# Qunyin_mmWave_mainIOs.net
KiCad netlist of a schematic drawn in Altium Designer
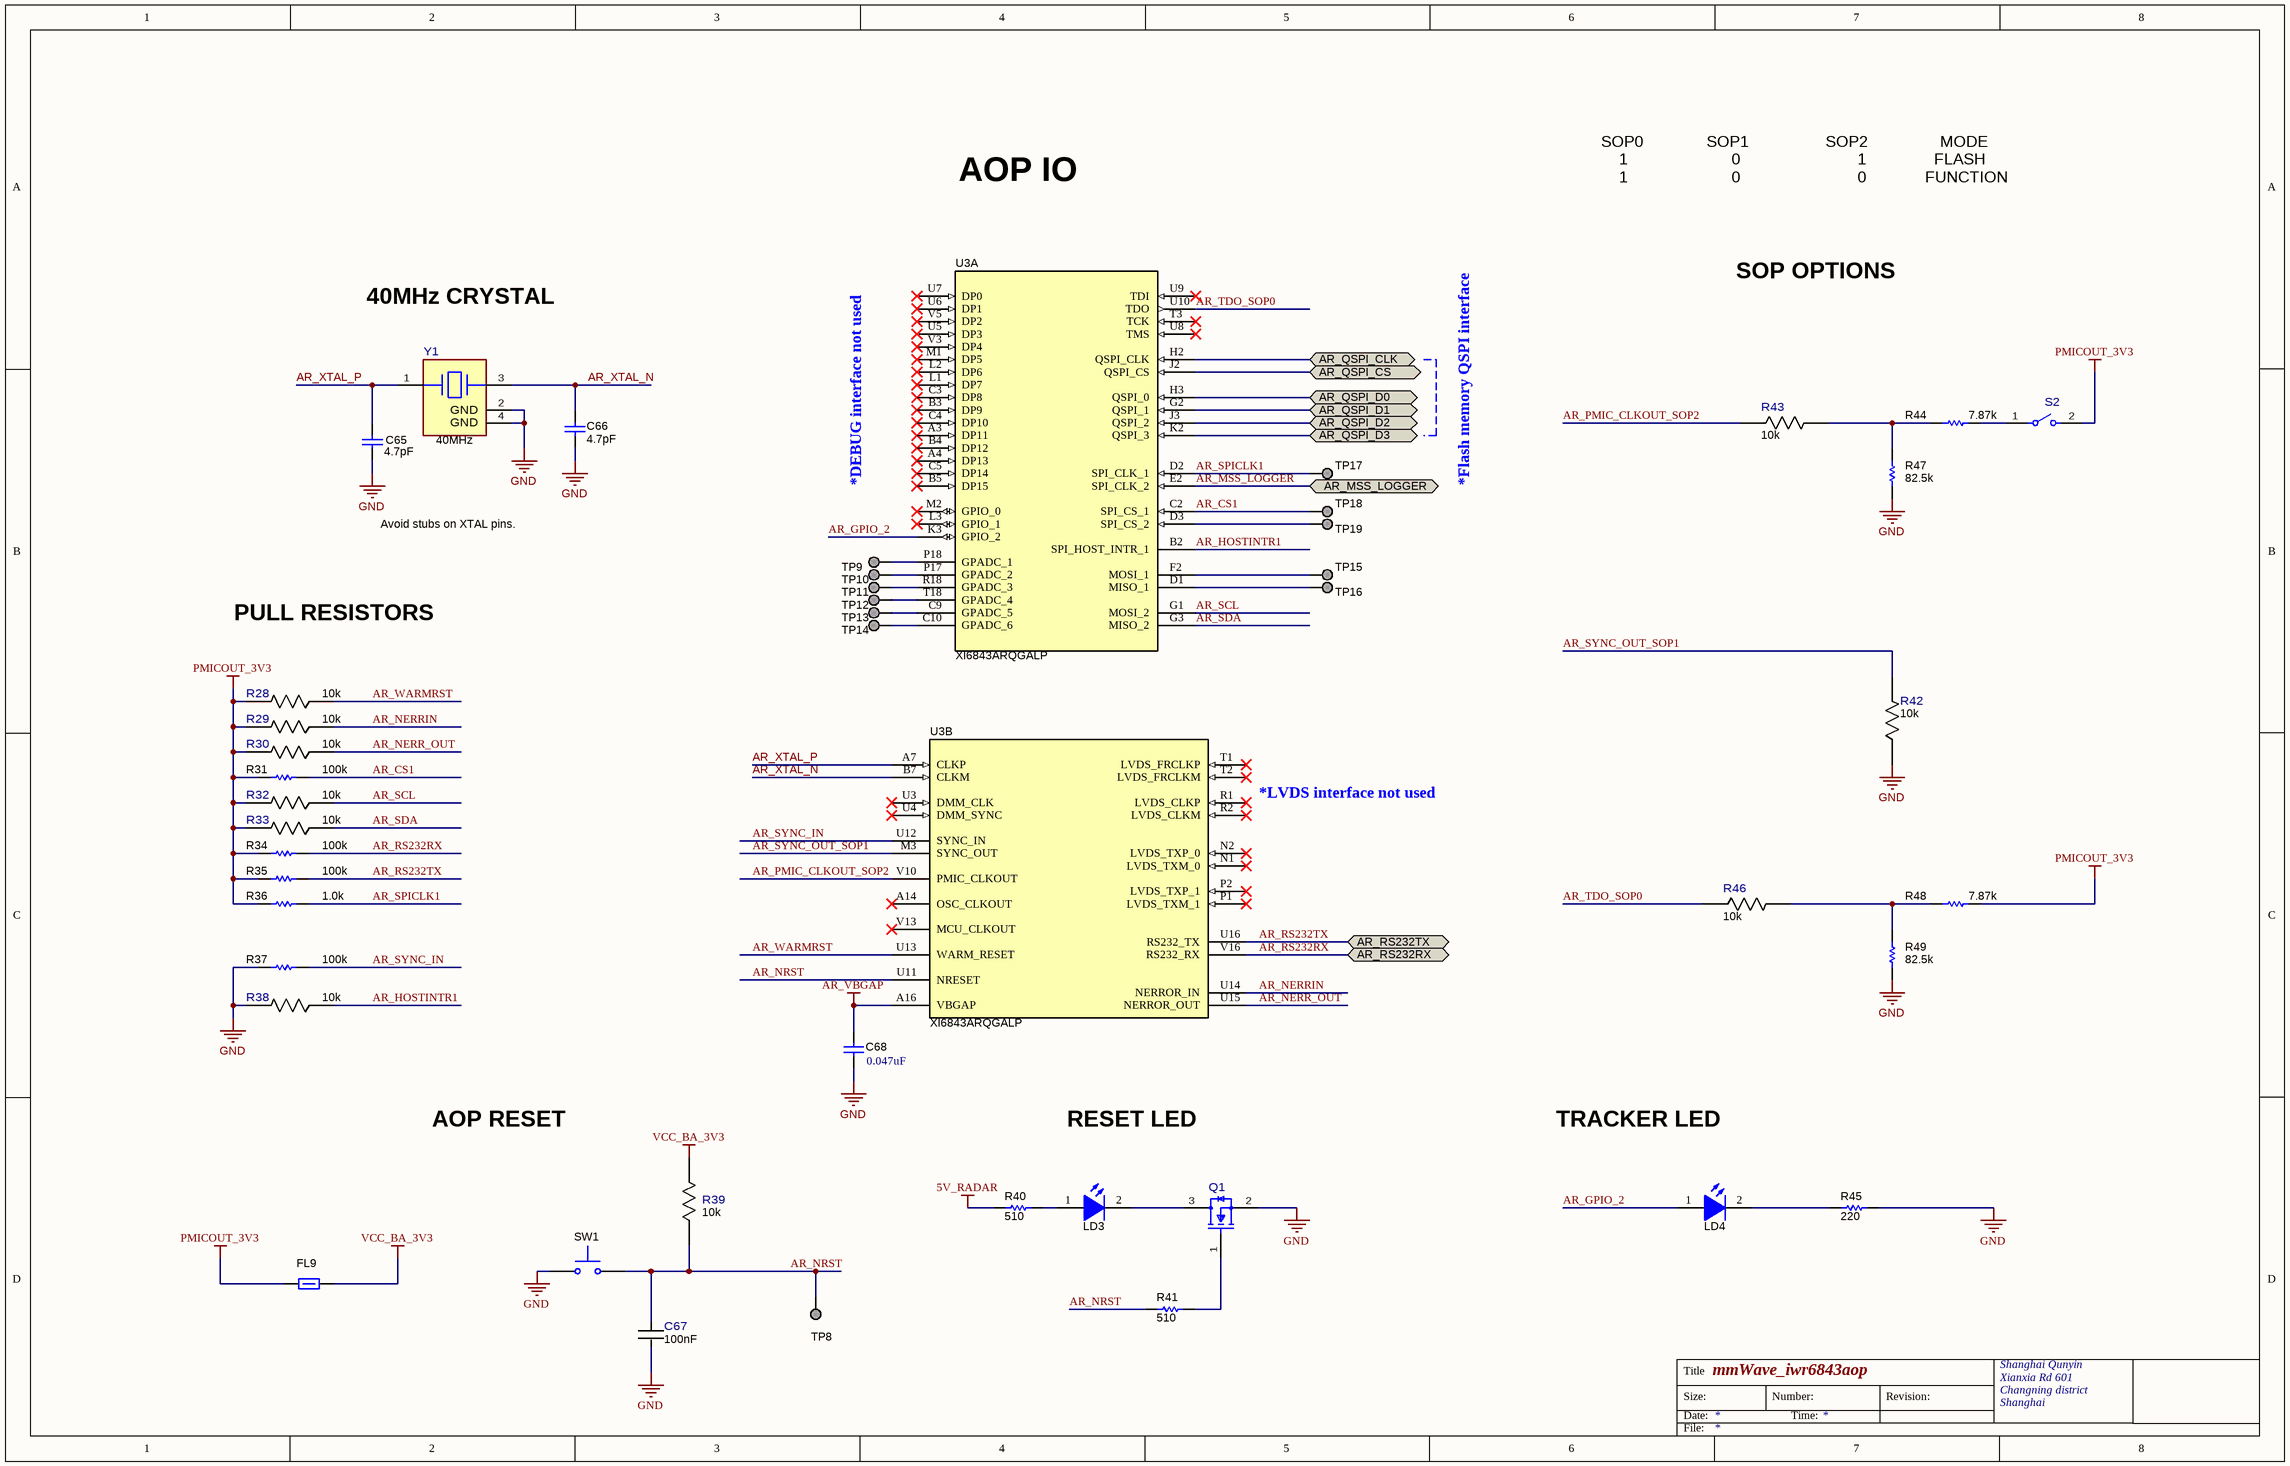
[diagram p0: Qunyin_mmWave_mainIOs.SchDoc]

(export (version "E")
  (design (tool "Eeschema 10.0.6"))
  (components
    (comp (ref "C65")
      (value "4.7pF")
      (footprint "0201_033L")
      (description "CAP, CERM, 4.7 pF, 50 V,+/- 3%, C0G/NP0, 0201")
      (fields (field (name "MANUFACTURER") "MuRata") (field (name "PARTNUMBER") "GRM0335C1H4R7BA01D"))
      (libsource (lib "Altium Vault - TI") (part "Capacitor"))
    )
    (comp (ref "C66")
      (value "4.7pF")
      (footprint "0201_033L")
      (description "CAP, CERM, 4.7 pF, 50 V,+/- 3%, C0G/NP0, 0201")
      (fields (field (name "MANUFACTURER") "MuRata") (field (name "PARTNUMBER") "GRM0335C1H4R7BA01D"))
      (libsource (lib "Altium Vault - TI") (part "Capacitor"))
    )
    (comp (ref "C67")
      (value "GRM033R6YA104KE14D")
      (footprint "FP-GRM033R6YA104KE14D_0201 (0603 Metric)-IPC_C")
      (description "Cap Ceramic 0.1uF 35V X5R 10% Pad SMD 0201 85C T/R")
      (fields (field (name "CAP_F") "100nF") (field (name "MANUFACTURER") "Murata Electronics North America"))
      (libsource (lib "Altium Vault - TI") (part "SYM-B32642B0223J"))
    )
    (comp (ref "C68")
      (value "GRM033R61C473KE84D")
      (footprint "0201_033L")
      (description "CAP, CERM, 0.047 uF, 16 V, +/- 10%, X5R, 0201")
      (fields
        (field (name "MANUFACTURER") "MuRata")
        (field (name "VALUEDISPLAYED") "0.047uF")
        (field (name "PUBLISHER") "Texas Instruments")
      )
      (libsource (lib "Altium Vault - TI") (part "Capacitor"))
    )
    (comp (ref "FL9")
      (value "BLM15PD300SZ1D")
      (footprint "0402L")
      (description "Inductor, Ferrite Bead, Ferrite, 2.2 A, 0.035 ohm, AEC-Q200 Grade 1, SMD")
      (fields (field (name "MANUFACTURER") "MuRata") (field (name "PUBLISHER") "Texas Instruments"))
      (libsource (lib "Altium Vault - TI") (part "Ferrite_Bead"))
    )
    (comp (ref "LD3")
      (value "APHHS1005CGCK")
      (footprint "APHHS1005_Green")
      (description "LED, Green, SMD")
      (fields (field (name "MANUFACTURER") "Kingbright"))
      (libsource (lib "Altium Vault - TI") (part "LED"))
    )
    (comp (ref "LD4")
      (value "APHHS1005CGCK")
      (footprint "APHHS1005_Green")
      (description "LED, Green, SMD")
      (fields (field (name "MANUFACTURER") "Kingbright"))
      (libsource (lib "Altium Vault - TI") (part "LED"))
    )
    (comp (ref "Q1")
      (value "BSS123-7-F")
      (footprint "FP-BSS123-7-F_SOT23-IPC_C")
      (description "MOSFET N-CH 100V 170MA SOT23-3")
      (fields (field (name "MANUFACTURER") "Diodes Incorporated"))
      (libsource (lib "Altium Vault - TI") (part "SYM-BSS123-7-F"))
    )
    (comp (ref "R28")
      (value "RR0306P-103-D")
      (footprint "FP-RR0306P-103-D_0201-IPC_C")
      (description "10 kOhms ±0.5% 0.05W, 1/20W Chip Resistor 0201 (0603 Metric)  Thin Film")
      (fields (field (name "MANUFACTURER") "Susumu") (field (name "RES_OHM") "10k"))
      (libsource (lib "Altium Vault - TI") (part "SYM-PMR18EZPJ000"))
    )
    (comp (ref "R29")
      (value "RR0306P-103-D")
      (footprint "FP-RR0306P-103-D_0201-IPC_C")
      (description "10 kOhms ±0.5% 0.05W, 1/20W Chip Resistor 0201 (0603 Metric)  Thin Film")
      (fields (field (name "MANUFACTURER") "Susumu") (field (name "RES_OHM") "10k"))
      (libsource (lib "Altium Vault - TI") (part "SYM-PMR18EZPJ000"))
    )
    (comp (ref "R30")
      (value "RR0306P-103-D")
      (footprint "FP-RR0306P-103-D_0201-IPC_C")
      (description "10 kOhms ±0.5% 0.05W, 1/20W Chip Resistor 0201 (0603 Metric)  Thin Film")
      (fields (field (name "MANUFACTURER") "Susumu") (field (name "RES_OHM") "10k"))
      (libsource (lib "Altium Vault - TI") (part "SYM-PMR18EZPJ000"))
    )
    (comp (ref "R31")
      (value "100k")
      (footprint "0201L")
      (description "RES, 100 k, 1%, 0.05 W, 0201")
      (fields (field (name "MANUFACTURER") "Vishay-Dale") (field (name "PARTNUMBER") "CRCW0201100KFKED"))
      (libsource (lib "Altium Vault - TI") (part "Resistor"))
    )
    (comp (ref "R32")
      (value "RR0306P-103-D")
      (footprint "FP-RR0306P-103-D_0201-IPC_C")
      (description "10 kOhms ±0.5% 0.05W, 1/20W Chip Resistor 0201 (0603 Metric)  Thin Film")
      (fields (field (name "MANUFACTURER") "Susumu") (field (name "RES_OHM") "10k"))
      (libsource (lib "Altium Vault - TI") (part "SYM-PMR18EZPJ000"))
    )
    (comp (ref "R33")
      (value "RR0306P-103-D")
      (footprint "FP-RR0306P-103-D_0201-IPC_C")
      (description "10 kOhms ±0.5% 0.05W, 1/20W Chip Resistor 0201 (0603 Metric)  Thin Film")
      (fields (field (name "MANUFACTURER") "Susumu") (field (name "RES_OHM") "10k"))
      (libsource (lib "Altium Vault - TI") (part "SYM-PMR18EZPJ000"))
    )
    (comp (ref "R34")
      (value "100k")
      (footprint "0201L")
      (description "RES, 100 k, 1%, 0.05 W, 0201")
      (fields (field (name "MANUFACTURER") "Vishay-Dale") (field (name "PARTNUMBER") "CRCW0201100KFKED"))
      (libsource (lib "Altium Vault - TI") (part "Resistor"))
    )
    (comp (ref "R35")
      (value "100k")
      (footprint "0201L")
      (description "RES, 100 k, 1%, 0.05 W, 0201")
      (fields (field (name "MANUFACTURER") "Vishay-Dale") (field (name "PARTNUMBER") "CRCW0201100KFKED"))
      (libsource (lib "Altium Vault - TI") (part "Resistor"))
    )
    (comp (ref "R36")
      (value "1.0k")
      (footprint "0201L")
      (description "RES, 1.0 k, 5%, 0.05 W, 0201")
      (fields
        (field (name "MANUFACTURER") "Yageo America")
        (field (name "PARTNUMBER") "RC0201JR-071KL")
        (field (name "PUBLISHER") "Texas Instruments")
      )
      (libsource (lib "Altium Vault - TI") (part "Resistor"))
    )
    (comp (ref "R37")
      (value "100k")
      (footprint "0201L")
      (description "RES, 100 k, 1%, 0.05 W, 0201")
      (fields (field (name "MANUFACTURER") "Vishay-Dale") (field (name "PARTNUMBER") "CRCW0201100KFKED"))
      (libsource (lib "Altium Vault - TI") (part "Resistor"))
    )
    (comp (ref "R38")
      (value "RR0306P-103-D")
      (footprint "FP-RR0306P-103-D_0201-IPC_C")
      (description "10 kOhms ±0.5% 0.05W, 1/20W Chip Resistor 0201 (0603 Metric)  Thin Film")
      (fields (field (name "MANUFACTURER") "Susumu") (field (name "RES_OHM") "10k"))
      (libsource (lib "Altium Vault - TI") (part "SYM-PMR18EZPJ000"))
    )
    (comp (ref "R39")
      (value "RR0306P-103-D")
      (footprint "FP-RR0306P-103-D_0201-IPC_C")
      (description "10 kOhms ±0.5% 0.05W, 1/20W Chip Resistor 0201 (0603 Metric)  Thin Film")
      (fields (field (name "MANUFACTURER") "Susumu") (field (name "RES_OHM") "10k"))
      (libsource (lib "Altium Vault - TI") (part "SYM-PMR18EZPJ000"))
    )
    (comp (ref "R40")
      (value "510")
      (footprint "0201L")
      (description "RES, 510, 5%, 0.05 W, 0201")
      (fields
        (field (name "MANUFACTURER") "Yageo America")
        (field (name "PARTNUMBER") "RC0201JR-07510RL")
        (field (name "PUBLISHER") "Texas Instruments")
      )
      (libsource (lib "Altium Vault - TI") (part "Resistor"))
    )
    (comp (ref "R41")
      (value "510")
      (footprint "0201L")
      (description "RES, 510, 5%, 0.05 W, 0201")
      (fields
        (field (name "MANUFACTURER") "Yageo America")
        (field (name "PARTNUMBER") "RC0201JR-07510RL")
        (field (name "PUBLISHER") "Texas Instruments")
      )
      (libsource (lib "Altium Vault - TI") (part "Resistor"))
    )
    (comp (ref "R42")
      (value "RR0306P-103-D")
      (footprint "FP-RR0306P-103-D_0201-IPC_C")
      (description "10 kOhms ±0.5% 0.05W, 1/20W Chip Resistor 0201 (0603 Metric)  Thin Film")
      (fields (field (name "MANUFACTURER") "Susumu") (field (name "RES_OHM") "10k"))
      (libsource (lib "Altium Vault - TI") (part "SYM-PMR18EZPJ000"))
    )
    (comp (ref "R43")
      (value "RR0306P-103-D")
      (footprint "FP-RR0306P-103-D_0201-IPC_C")
      (description "10 kOhms ±0.5% 0.05W, 1/20W Chip Resistor 0201 (0603 Metric)  Thin Film")
      (fields (field (name "MANUFACTURER") "Susumu") (field (name "RES_OHM") "10k"))
      (libsource (lib "Altium Vault - TI") (part "SYM-PMR18EZPJ000"))
    )
    (comp (ref "R44")
      (value "7.87k")
      (footprint "0201L")
      (description "RES, 7.87 k, 1%, 0.05 W, 0201")
      (fields
        (field (name "MANUFACTURER") "Yageo America")
        (field (name "PARTNUMBER") "RC0201FR-077K87L")
        (field (name "PUBLISHER") "Texas Instruments")
      )
      (libsource (lib "Altium Vault - TI") (part "Resistor"))
    )
    (comp (ref "R45")
      (value "220")
      (footprint "0201L")
      (description "RES, 220, 5%, 0.05 W, 0201")
      (fields
        (field (name "MANUFACTURER") "Yageo America")
        (field (name "PARTNUMBER") "RC0201JR-07220RL")
        (field (name "PUBLISHER") "Texas Instruments")
      )
      (libsource (lib "Altium Vault - TI") (part "Resistor"))
    )
    (comp (ref "R46")
      (value "RR0306P-103-D")
      (footprint "FP-RR0306P-103-D_0201-IPC_C")
      (description "10 kOhms ±0.5% 0.05W, 1/20W Chip Resistor 0201 (0603 Metric)  Thin Film")
      (fields (field (name "MANUFACTURER") "Susumu") (field (name "RES_OHM") "10k"))
      (libsource (lib "Altium Vault - TI") (part "SYM-PMR18EZPJ000"))
    )
    (comp (ref "R47")
      (value "82.5k")
      (footprint "0201L")
      (description "RES, 82.5 k, 1%, 0.05 W, 0201")
      (fields
        (field (name "MANUFACTURER") "Yageo America")
        (field (name "PARTNUMBER") "RC0201FR-0782K5L")
        (field (name "PUBLISHER") "Texas Instruments")
      )
      (libsource (lib "Altium Vault - TI") (part "Resistor"))
    )
    (comp (ref "R48")
      (value "7.87k")
      (footprint "0201L")
      (description "RES, 7.87 k, 1%, 0.05 W, 0201")
      (fields
        (field (name "MANUFACTURER") "Yageo America")
        (field (name "PARTNUMBER") "RC0201FR-077K87L")
        (field (name "PUBLISHER") "Texas Instruments")
      )
      (libsource (lib "Altium Vault - TI") (part "Resistor"))
    )
    (comp (ref "R49")
      (value "82.5k")
      (footprint "0201L")
      (description "RES, 82.5 k, 1%, 0.05 W, 0201")
      (fields
        (field (name "MANUFACTURER") "Yageo America")
        (field (name "PARTNUMBER") "RC0201FR-0782K5L")
        (field (name "PUBLISHER") "Texas Instruments")
      )
      (libsource (lib "Altium Vault - TI") (part "Resistor"))
    )
    (comp (ref "S2")
      (value "CHS-01TA")
      (footprint "FP-CHS-01TA_SMT_SW_5MM4_2MM5-MFG")
      (description "SWITCH SLIDE DIP SPST 100MA 6V")
      (fields (field (name "MANUFACTURER") "Nidec Copal Electronics"))
      (libsource (lib "Altium Vault - TI") (part "SYM-PTS635SK25SM"))
    )
    (comp (ref "SW1")
      (value "B3U-1000P")
      (footprint "SW_B3U-1000P")
      (description "SWITCH TACTILE SPST-NO 0.05A 12V")
      (fields
        (field (name "MANUFACTURER") "Omron Electronic Components")
        (field (name "PUBLISHER") "Texas Instruments")
      )
      (libsource (lib "Altium Vault - TI") (part "Switch_PushButton"))
    )
    (comp (ref "TP8")
      (value "TESTPOINT")
      (footprint "TP_25MIL-SMT")
      (description "TEST POINT.  No entry in BOM.")
      (libsource (lib "Altium Vault - TI") (part "TESTPOINT"))
    )
    (comp (ref "TP9")
      (value "TESTPOINT")
      (footprint "TP_25MIL-SMT")
      (description "TEST POINT.  No entry in BOM.")
      (libsource (lib "Altium Vault - TI") (part "TESTPOINT"))
    )
    (comp (ref "TP10")
      (value "TESTPOINT")
      (footprint "TP_25MIL-SMT")
      (description "TEST POINT.  No entry in BOM.")
      (libsource (lib "Altium Vault - TI") (part "TESTPOINT"))
    )
    (comp (ref "TP11")
      (value "TESTPOINT")
      (footprint "TP_25MIL-SMT")
      (description "TEST POINT.  No entry in BOM.")
      (libsource (lib "Altium Vault - TI") (part "TESTPOINT"))
    )
    (comp (ref "TP12")
      (value "TESTPOINT")
      (footprint "TP_25MIL-SMT")
      (description "TEST POINT.  No entry in BOM.")
      (libsource (lib "Altium Vault - TI") (part "TESTPOINT"))
    )
    (comp (ref "TP13")
      (value "TESTPOINT")
      (footprint "TP_25MIL-SMT")
      (description "TEST POINT.  No entry in BOM.")
      (libsource (lib "Altium Vault - TI") (part "TESTPOINT"))
    )
    (comp (ref "TP14")
      (value "TESTPOINT")
      (footprint "TP_25MIL-SMT")
      (description "TEST POINT.  No entry in BOM.")
      (libsource (lib "Altium Vault - TI") (part "TESTPOINT"))
    )
    (comp (ref "TP15")
      (value "TESTPOINT")
      (footprint "TP_25MIL-SMT")
      (description "TEST POINT.  No entry in BOM.")
      (libsource (lib "Altium Vault - TI") (part "TESTPOINT"))
    )
    (comp (ref "TP16")
      (value "TESTPOINT")
      (footprint "TP_25MIL-SMT")
      (description "TEST POINT.  No entry in BOM.")
      (libsource (lib "Altium Vault - TI") (part "TESTPOINT"))
    )
    (comp (ref "TP17")
      (value "TESTPOINT")
      (footprint "TP_25MIL-SMT")
      (description "TEST POINT.  No entry in BOM.")
      (libsource (lib "Altium Vault - TI") (part "TESTPOINT"))
    )
    (comp (ref "TP18")
      (value "TESTPOINT")
      (footprint "TP_25MIL-SMT")
      (description "TEST POINT.  No entry in BOM.")
      (libsource (lib "Altium Vault - TI") (part "TESTPOINT"))
    )
    (comp (ref "TP19")
      (value "TESTPOINT")
      (footprint "TP_25MIL-SMT")
      (description "TEST POINT.  No entry in BOM.")
      (libsource (lib "Altium Vault - TI") (part "TESTPOINT"))
    )
    (comp (ref "U3")
      (value "XI6843ARQGALP")
      (footprint "ALP0180A")
      (description "XI6843ARQGALP, ALP0180A (BGA-180)")
      (fields (field (name "MANUFACTURER") "Texas Instruments") (field (name "PARTNUMBER") "XI6843ARQGALP"))
      (libsource (lib "Altium Vault - TI") (part "XI6843ARQGALP"))
    )
    (comp (ref "Y1")
      (value "CX2016DB40000D0FLJCC")
      (footprint "FP-CX2016DB40000D0FLJCC_SMT_2MM0_1MM6-MFG")
      (description "CRYSTAL 40.0000MHZ 8PF SMD")
      (fields
        (field (name "FREQUENCY_FIXED") "40MHz")
        (field (name "MANUFACTURER") "Kyocera International Inc. Electronic Components")
      )
      (libsource (lib "Altium Vault - TI") (part "SYM-CX2016DB40000D0FLJCC"))
    )
  )
  (nets
    (net (code "1") (name "/AR_CS1") (class "Default")
      (node (ref "R31") (pin "2") (pinfunction "2_2") (pintype "passive"))
      (node (ref "TP18") (pin "1") (pintype "passive"))
      (node (ref "U3") (pin "C2") (pinfunction "SPI_CS_1_C2") (pintype "input"))
    )
    (net (code "2") (name "/AR_GPIO_2") (class "Default")
      (node (ref "LD4") (pin "1") (pinfunction "A_1") (pintype "passive"))
      (node (ref "U3") (pin "K3") (pinfunction "GPIO_2_K3") (pintype "bidirectional"))
    )
    (net (code "3") (name "/AR_HOSTINTR1") (class "Default")
      (node (ref "R38") (pin "1") (pinfunction "1_1") (pintype "passive"))
      (node (ref "U3") (pin "B2") (pinfunction "SPI_HOST_INTR_1_B2") (pintype "passive"))
    )
    (net (code "4") (name "/AR_MSS_LOGGER") (class "Default")
      (node (ref "U3") (pin "E2") (pinfunction "SPI_CLK_2_E2") (pintype "input"))
    )
    (net (code "5") (name "/AR_NERRIN") (class "Default")
      (node (ref "R29") (pin "1") (pinfunction "1_1") (pintype "passive"))
      (node (ref "U3") (pin "U14") (pinfunction "NERROR_IN_U14") (pintype "passive"))
    )
    (net (code "6") (name "/AR_NERR_OUT") (class "Default")
      (node (ref "R30") (pin "1") (pinfunction "1_1") (pintype "passive"))
      (node (ref "U3") (pin "U15") (pinfunction "NERROR_OUT_U15") (pintype "passive"))
    )
    (net (code "7") (name "/AR_NRST") (class "Default")
      (node (ref "C67") (pin "1") (pinfunction "1_1") (pintype "passive"))
      (node (ref "R39") (pin "1") (pinfunction "1_1") (pintype "passive"))
      (node (ref "R41") (pin "1") (pinfunction "1_1") (pintype "passive"))
      (node (ref "SW1") (pin "1") (pinfunction "1_1") (pintype "passive"))
      (node (ref "TP8") (pin "1") (pintype "passive"))
      (node (ref "U3") (pin "U11") (pinfunction "NRESET_U11") (pintype "passive"))
    )
    (net (code "8") (name "/AR_PMIC_CLKOUT_SOP2") (class "Default")
      (node (ref "R43") (pin "1") (pinfunction "1_1") (pintype "passive"))
      (node (ref "U3") (pin "V10") (pinfunction "PMIC_CLKOUT_V10") (pintype "passive"))
    )
    (net (code "9") (name "/AR_QSPI_CLK") (class "Default")
      (node (ref "U3") (pin "H2") (pinfunction "QSPI_CLK_H2") (pintype "input"))
    )
    (net (code "10") (name "/AR_QSPI_CS") (class "Default")
      (node (ref "U3") (pin "J2") (pinfunction "QSPI_CS_J2") (pintype "input"))
    )
    (net (code "11") (name "/AR_QSPI_D0") (class "Default")
      (node (ref "U3") (pin "H3") (pinfunction "QSPI_0_H3") (pintype "input"))
    )
    (net (code "12") (name "/AR_QSPI_D1") (class "Default")
      (node (ref "U3") (pin "G2") (pinfunction "QSPI_1_G2") (pintype "input"))
    )
    (net (code "13") (name "/AR_QSPI_D2") (class "Default")
      (node (ref "U3") (pin "J3") (pinfunction "QSPI_2_J3") (pintype "input"))
    )
    (net (code "14") (name "/AR_QSPI_D3") (class "Default")
      (node (ref "U3") (pin "K2") (pinfunction "QSPI_3_K2") (pintype "input"))
    )
    (net (code "15") (name "/AR_RS232RX") (class "Default")
      (node (ref "R34") (pin "2") (pinfunction "2_2") (pintype "passive"))
      (node (ref "U3") (pin "V16") (pinfunction "RS232_RX_V16") (pintype "passive"))
    )
    (net (code "16") (name "/AR_RS232TX") (class "Default")
      (node (ref "R35") (pin "2") (pinfunction "2_2") (pintype "passive"))
      (node (ref "U3") (pin "U16") (pinfunction "RS232_TX_U16") (pintype "passive"))
    )
    (net (code "17") (name "/AR_SCL") (class "Default")
      (node (ref "R32") (pin "1") (pinfunction "1_1") (pintype "passive"))
      (node (ref "U3") (pin "G1") (pinfunction "MOSI_2_G1") (pintype "passive"))
    )
    (net (code "18") (name "/AR_SDA") (class "Default")
      (node (ref "R33") (pin "1") (pinfunction "1_1") (pintype "passive"))
      (node (ref "U3") (pin "G3") (pinfunction "MISO_2_G3") (pintype "passive"))
    )
    (net (code "19") (name "/AR_SPICLK1") (class "Default")
      (node (ref "R36") (pin "2") (pinfunction "2_2") (pintype "passive"))
      (node (ref "TP17") (pin "1") (pintype "passive"))
      (node (ref "U3") (pin "D2") (pinfunction "SPI_CLK_1_D2") (pintype "input"))
    )
    (net (code "20") (name "/AR_SYNC_IN") (class "Default")
      (node (ref "R37") (pin "2") (pinfunction "2_2") (pintype "passive"))
      (node (ref "U3") (pin "U12") (pinfunction "SYNC_IN_U12") (pintype "passive"))
    )
    (net (code "21") (name "/AR_SYNC_OUT_SOP1") (class "Default")
      (node (ref "R42") (pin "2") (pinfunction "2_2") (pintype "passive"))
      (node (ref "U3") (pin "M3") (pinfunction "SYNC_OUT_M3") (pintype "passive"))
    )
    (net (code "22") (name "/AR_TDO_SOP0") (class "Default")
      (node (ref "R46") (pin "1") (pinfunction "1_1") (pintype "passive"))
      (node (ref "U3") (pin "U10") (pinfunction "TDO_U10") (pintype "output"))
    )
    (net (code "23") (name "/AR_WARMRST") (class "Default")
      (node (ref "R28") (pin "1") (pinfunction "1_1") (pintype "passive"))
      (node (ref "U3") (pin "U13") (pinfunction "WARM_RESET_U13") (pintype "passive"))
    )
    (net (code "24") (name "/AR_XTAL_N") (class "Default")
      (node (ref "C66") (pin "2") (pinfunction "2_2") (pintype "passive"))
      (node (ref "U3") (pin "B7") (pinfunction "CLKM_B7") (pintype "input"))
      (node (ref "Y1") (pin "3") (pinfunction "3_3") (pintype "passive"))
    )
    (net (code "25") (name "/AR_XTAL_P") (class "Default")
      (node (ref "C65") (pin "2") (pinfunction "2_2") (pintype "passive"))
      (node (ref "U3") (pin "A7") (pinfunction "CLKP_A7") (pintype "input"))
      (node (ref "Y1") (pin "1") (pinfunction "1_1") (pintype "passive"))
    )
    (net (code "26") (name "5V_RADAR") (class "Default")
      (node (ref "R40") (pin "1") (pinfunction "1_1") (pintype "passive"))
    )
    (net (code "27") (name "AR_VBGAP") (class "Default")
      (node (ref "C68") (pin "1") (pinfunction "1_1") (pintype "passive"))
      (node (ref "U3") (pin "A16") (pinfunction "VBGAP_A16") (pintype "passive"))
    )
    (net (code "28") (name "GND") (class "Default")
      (node (ref "C65") (pin "1") (pinfunction "1_1") (pintype "passive"))
      (node (ref "C66") (pin "1") (pinfunction "1_1") (pintype "passive"))
      (node (ref "C67") (pin "2") (pinfunction "2_2") (pintype "passive"))
      (node (ref "C68") (pin "2") (pinfunction "2_2") (pintype "passive"))
      (node (ref "Q1") (pin "2") (pinfunction "S_2") (pintype "passive"))
      (node (ref "R37") (pin "1") (pinfunction "1_1") (pintype "passive"))
      (node (ref "R38") (pin "2") (pinfunction "2_2") (pintype "passive"))
      (node (ref "R42") (pin "1") (pinfunction "1_1") (pintype "passive"))
      (node (ref "R45") (pin "1") (pinfunction "1_1") (pintype "passive"))
      (node (ref "R47") (pin "1") (pinfunction "1_1") (pintype "passive"))
      (node (ref "R49") (pin "1") (pinfunction "1_1") (pintype "passive"))
      (node (ref "SW1") (pin "2") (pinfunction "2_2") (pintype "passive"))
      (node (ref "Y1") (pin "2") (pinfunction "GND_2") (pintype "power_in"))
      (node (ref "Y1") (pin "4") (pinfunction "GND_4") (pintype "power_in"))
    )
    (net (code "29") (name "Net-(LD3-A)") (class "Default")
      (node (ref "LD3") (pin "1") (pinfunction "A_1") (pintype "passive"))
      (node (ref "R40") (pin "2") (pinfunction "2_2") (pintype "passive"))
    )
    (net (code "30") (name "Net-(LD3-K)") (class "Default")
      (node (ref "LD3") (pin "2") (pinfunction "K_2") (pintype "passive"))
      (node (ref "Q1") (pin "3") (pinfunction "D_3") (pintype "passive"))
    )
    (net (code "31") (name "Net-(LD4-K)") (class "Default")
      (node (ref "LD4") (pin "2") (pinfunction "K_2") (pintype "passive"))
      (node (ref "R45") (pin "2") (pinfunction "2_2") (pintype "passive"))
    )
    (net (code "32") (name "Net-(Q1-G)") (class "Default")
      (node (ref "Q1") (pin "1") (pinfunction "G_1") (pintype "passive"))
      (node (ref "R41") (pin "2") (pinfunction "2_2") (pintype "passive"))
    )
    (net (code "33") (name "Net-(R43-Pad2)") (class "Default")
      (node (ref "R43") (pin "2") (pinfunction "2_2") (pintype "passive"))
      (node (ref "R44") (pin "2") (pinfunction "2_2") (pintype "passive"))
      (node (ref "R47") (pin "2") (pinfunction "2_2") (pintype "passive"))
    )
    (net (code "34") (name "Net-(R44-Pad1)") (class "Default")
      (node (ref "R44") (pin "1") (pinfunction "1_1") (pintype "passive"))
      (node (ref "S2") (pin "1") (pinfunction "1_1") (pintype "passive"))
    )
    (net (code "35") (name "Net-(R46-Pad2)") (class "Default")
      (node (ref "R46") (pin "2") (pinfunction "2_2") (pintype "passive"))
      (node (ref "R48") (pin "2") (pinfunction "2_2") (pintype "passive"))
      (node (ref "R49") (pin "2") (pinfunction "2_2") (pintype "passive"))
    )
    (net (code "36") (name "Net-(U3A-GPADC_1)") (class "Default")
      (node (ref "TP9") (pin "1") (pintype "passive"))
      (node (ref "U3") (pin "P18") (pinfunction "GPADC_1_P18") (pintype "passive"))
    )
    (net (code "37") (name "Net-(U3A-GPADC_2)") (class "Default")
      (node (ref "TP10") (pin "1") (pintype "passive"))
      (node (ref "U3") (pin "P17") (pinfunction "GPADC_2_P17") (pintype "passive"))
    )
    (net (code "38") (name "Net-(U3A-GPADC_3)") (class "Default")
      (node (ref "TP11") (pin "1") (pintype "passive"))
      (node (ref "U3") (pin "R18") (pinfunction "GPADC_3_R18") (pintype "passive"))
    )
    (net (code "39") (name "Net-(U3A-GPADC_4)") (class "Default")
      (node (ref "TP12") (pin "1") (pintype "passive"))
      (node (ref "U3") (pin "T18") (pinfunction "GPADC_4_T18") (pintype "passive"))
    )
    (net (code "40") (name "Net-(U3A-GPADC_5)") (class "Default")
      (node (ref "TP13") (pin "1") (pintype "passive"))
      (node (ref "U3") (pin "C9") (pinfunction "GPADC_5_C9") (pintype "passive"))
    )
    (net (code "41") (name "Net-(U3A-GPADC_6)") (class "Default")
      (node (ref "TP14") (pin "1") (pintype "passive"))
      (node (ref "U3") (pin "C10") (pinfunction "GPADC_6_C10") (pintype "passive"))
    )
    (net (code "42") (name "Net-(U3A-MISO_1)") (class "Default")
      (node (ref "TP16") (pin "1") (pintype "passive"))
      (node (ref "U3") (pin "D1") (pinfunction "MISO_1_D1") (pintype "passive"))
    )
    (net (code "43") (name "Net-(U3A-MOSI_1)") (class "Default")
      (node (ref "TP15") (pin "1") (pintype "passive"))
      (node (ref "U3") (pin "F2") (pinfunction "MOSI_1_F2") (pintype "passive"))
    )
    (net (code "44") (name "Net-(U3A-SPI_CS_2)") (class "Default")
      (node (ref "TP19") (pin "1") (pintype "passive"))
      (node (ref "U3") (pin "D3") (pinfunction "SPI_CS_2_D3") (pintype "input"))
    )
    (net (code "45") (name "PMICOUT_3V3") (class "Default")
      (node (ref "FL9") (pin "1") (pinfunction "1_1") (pintype "passive"))
      (node (ref "R28") (pin "2") (pinfunction "2_2") (pintype "passive"))
      (node (ref "R29") (pin "2") (pinfunction "2_2") (pintype "passive"))
      (node (ref "R30") (pin "2") (pinfunction "2_2") (pintype "passive"))
      (node (ref "R31") (pin "1") (pinfunction "1_1") (pintype "passive"))
      (node (ref "R32") (pin "2") (pinfunction "2_2") (pintype "passive"))
      (node (ref "R33") (pin "2") (pinfunction "2_2") (pintype "passive"))
      (node (ref "R34") (pin "1") (pinfunction "1_1") (pintype "passive"))
      (node (ref "R35") (pin "1") (pinfunction "1_1") (pintype "passive"))
      (node (ref "R36") (pin "1") (pinfunction "1_1") (pintype "passive"))
      (node (ref "R48") (pin "1") (pinfunction "1_1") (pintype "passive"))
      (node (ref "S2") (pin "2") (pinfunction "2_2") (pintype "passive"))
    )
    (net (code "46") (name "VCC_BA_3V3") (class "Default")
      (node (ref "FL9") (pin "2") (pinfunction "2_2") (pintype "passive"))
      (node (ref "R39") (pin "2") (pinfunction "2_2") (pintype "passive"))
    )
    (net (code "47") (name "unconnected-(U3A-DP0-PadU7)") (class "Default")
      (node (ref "U3") (pin "U7") (pinfunction "DP0_U7") (pintype "input+no_connect"))
    )
    (net (code "48") (name "unconnected-(U3A-DP1-PadU6)") (class "Default")
      (node (ref "U3") (pin "U6") (pinfunction "DP1_U6") (pintype "input+no_connect"))
    )
    (net (code "49") (name "unconnected-(U3A-DP2-PadV5)") (class "Default")
      (node (ref "U3") (pin "V5") (pinfunction "DP2_V5") (pintype "input+no_connect"))
    )
    (net (code "50") (name "unconnected-(U3A-DP3-PadU5)") (class "Default")
      (node (ref "U3") (pin "U5") (pinfunction "DP3_U5") (pintype "input+no_connect"))
    )
    (net (code "51") (name "unconnected-(U3A-DP4-PadV3)") (class "Default")
      (node (ref "U3") (pin "V3") (pinfunction "DP4_V3") (pintype "input+no_connect"))
    )
    (net (code "52") (name "unconnected-(U3A-DP5-PadM1)") (class "Default")
      (node (ref "U3") (pin "M1") (pinfunction "DP5_M1") (pintype "input+no_connect"))
    )
    (net (code "53") (name "unconnected-(U3A-DP6-PadL2)") (class "Default")
      (node (ref "U3") (pin "L2") (pinfunction "DP6_L2") (pintype "input+no_connect"))
    )
    (net (code "54") (name "unconnected-(U3A-DP7-PadL1)") (class "Default")
      (node (ref "U3") (pin "L1") (pinfunction "DP7_L1") (pintype "input+no_connect"))
    )
    (net (code "55") (name "unconnected-(U3A-DP8-PadC3)") (class "Default")
      (node (ref "U3") (pin "C3") (pinfunction "DP8_C3") (pintype "input+no_connect"))
    )
    (net (code "56") (name "unconnected-(U3A-DP9-PadB3)") (class "Default")
      (node (ref "U3") (pin "B3") (pinfunction "DP9_B3") (pintype "input+no_connect"))
    )
    (net (code "57") (name "unconnected-(U3A-DP10-PadC4)") (class "Default")
      (node (ref "U3") (pin "C4") (pinfunction "DP10_C4") (pintype "input+no_connect"))
    )
    (net (code "58") (name "unconnected-(U3A-DP11-PadA3)") (class "Default")
      (node (ref "U3") (pin "A3") (pinfunction "DP11_A3") (pintype "input+no_connect"))
    )
    (net (code "59") (name "unconnected-(U3A-DP12-PadB4)") (class "Default")
      (node (ref "U3") (pin "B4") (pinfunction "DP12_B4") (pintype "input+no_connect"))
    )
    (net (code "60") (name "unconnected-(U3A-DP13-PadA4)") (class "Default")
      (node (ref "U3") (pin "A4") (pinfunction "DP13_A4") (pintype "input+no_connect"))
    )
    (net (code "61") (name "unconnected-(U3A-DP14-PadC5)") (class "Default")
      (node (ref "U3") (pin "C5") (pinfunction "DP14_C5") (pintype "input+no_connect"))
    )
    (net (code "62") (name "unconnected-(U3A-DP15-PadB5)") (class "Default")
      (node (ref "U3") (pin "B5") (pinfunction "DP15_B5") (pintype "input+no_connect"))
    )
    (net (code "63") (name "unconnected-(U3A-GPIO_0-PadM2)") (class "Default")
      (node (ref "U3") (pin "M2") (pinfunction "GPIO_0_M2") (pintype "bidirectional+no_connect"))
    )
    (net (code "64") (name "unconnected-(U3A-GPIO_1-PadL3)") (class "Default")
      (node (ref "U3") (pin "L3") (pinfunction "GPIO_1_L3") (pintype "bidirectional+no_connect"))
    )
    (net (code "65") (name "unconnected-(U3A-TCK-PadT3)") (class "Default")
      (node (ref "U3") (pin "T3") (pinfunction "TCK_T3") (pintype "input+no_connect"))
    )
    (net (code "66") (name "unconnected-(U3A-TDI-PadU9)") (class "Default")
      (node (ref "U3") (pin "U9") (pinfunction "TDI_U9") (pintype "input+no_connect"))
    )
    (net (code "67") (name "unconnected-(U3A-TMS-PadU8)") (class "Default")
      (node (ref "U3") (pin "U8") (pinfunction "TMS_U8") (pintype "input+no_connect"))
    )
    (net (code "68") (name "unconnected-(U3B-DMM_CLK-PadU3)") (class "Default")
      (node (ref "U3") (pin "U3") (pinfunction "DMM_CLK_U3") (pintype "input+no_connect"))
    )
    (net (code "69") (name "unconnected-(U3B-DMM_SYNC-PadU4)") (class "Default")
      (node (ref "U3") (pin "U4") (pinfunction "DMM_SYNC_U4") (pintype "input+no_connect"))
    )
    (net (code "70") (name "unconnected-(U3B-LVDS_CLKM-PadR2)") (class "Default")
      (node (ref "U3") (pin "R2") (pinfunction "LVDS_CLKM_R2") (pintype "input+no_connect"))
    )
    (net (code "71") (name "unconnected-(U3B-LVDS_CLKP-PadR1)") (class "Default")
      (node (ref "U3") (pin "R1") (pinfunction "LVDS_CLKP_R1") (pintype "input+no_connect"))
    )
    (net (code "72") (name "unconnected-(U3B-LVDS_FRCLKM-PadT2)") (class "Default")
      (node (ref "U3") (pin "T2") (pinfunction "LVDS_FRCLKM_T2") (pintype "input+no_connect"))
    )
    (net (code "73") (name "unconnected-(U3B-LVDS_FRCLKP-PadT1)") (class "Default")
      (node (ref "U3") (pin "T1") (pinfunction "LVDS_FRCLKP_T1") (pintype "input+no_connect"))
    )
    (net (code "74") (name "unconnected-(U3B-LVDS_TXM_0-PadN1)") (class "Default")
      (node (ref "U3") (pin "N1") (pinfunction "LVDS_TXM_0_N1") (pintype "input+no_connect"))
    )
    (net (code "75") (name "unconnected-(U3B-LVDS_TXM_1-PadP1)") (class "Default")
      (node (ref "U3") (pin "P1") (pinfunction "LVDS_TXM_1_P1") (pintype "input+no_connect"))
    )
    (net (code "76") (name "unconnected-(U3B-LVDS_TXP_0-PadN2)") (class "Default")
      (node (ref "U3") (pin "N2") (pinfunction "LVDS_TXP_0_N2") (pintype "input+no_connect"))
    )
    (net (code "77") (name "unconnected-(U3B-LVDS_TXP_1-PadP2)") (class "Default")
      (node (ref "U3") (pin "P2") (pinfunction "LVDS_TXP_1_P2") (pintype "input+no_connect"))
    )
    (net (code "78") (name "unconnected-(U3B-MCU_CLKOUT-PadV13)") (class "Default")
      (node (ref "U3") (pin "V13") (pinfunction "MCU_CLKOUT_V13") (pintype "passive+no_connect"))
    )
    (net (code "79") (name "unconnected-(U3B-OSC_CLKOUT-PadA14)") (class "Default")
      (node (ref "U3") (pin "A14") (pinfunction "OSC_CLKOUT_A14") (pintype "passive+no_connect"))
    )
  )
)
